# relays2.net
KiCad netlist of a schematic drawn in Altium Designer
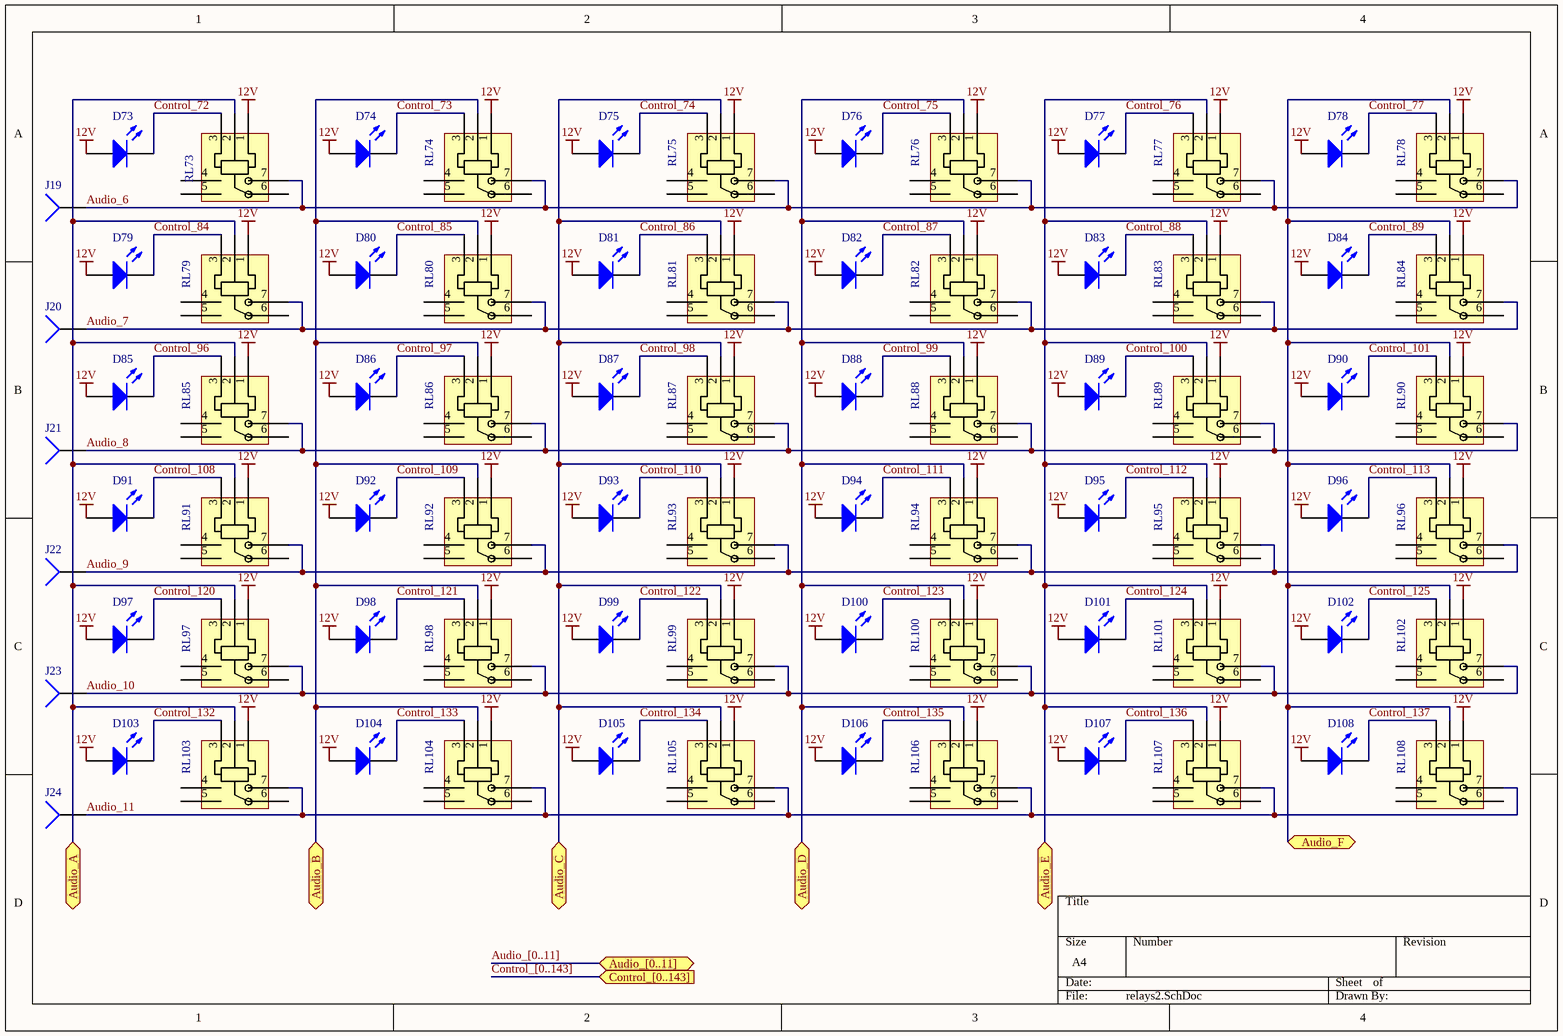
[diagram p0: relays2.SchDoc]

(export (version "E")
  (design (tool "Eeschema 10.0.6"))
  (components
    (comp (ref "D73")
      (value "LED0")
      (footprint "LED_round_5mm")
      (description "Typical INFRARED GaAs LED")
      (fields (field (name "PUBLISHER") "Altium Limited"))
      (libsource (lib "Miscellaneous Devices") (part "LED0"))
    )
    (comp (ref "D74")
      (value "LED0")
      (footprint "LED_round_5mm")
      (description "Typical INFRARED GaAs LED")
      (fields (field (name "PUBLISHER") "Altium Limited"))
      (libsource (lib "Miscellaneous Devices") (part "LED0"))
    )
    (comp (ref "D75")
      (value "LED0")
      (footprint "LED_round_5mm")
      (description "Typical INFRARED GaAs LED")
      (fields (field (name "PUBLISHER") "Altium Limited"))
      (libsource (lib "Miscellaneous Devices") (part "LED0"))
    )
    (comp (ref "D76")
      (value "LED0")
      (footprint "LED_round_5mm")
      (description "Typical INFRARED GaAs LED")
      (fields (field (name "PUBLISHER") "Altium Limited"))
      (libsource (lib "Miscellaneous Devices") (part "LED0"))
    )
    (comp (ref "D77")
      (value "LED0")
      (footprint "LED_round_5mm")
      (description "Typical INFRARED GaAs LED")
      (fields (field (name "PUBLISHER") "Altium Limited"))
      (libsource (lib "Miscellaneous Devices") (part "LED0"))
    )
    (comp (ref "D78")
      (value "LED0")
      (footprint "LED_round_5mm")
      (description "Typical INFRARED GaAs LED")
      (fields (field (name "PUBLISHER") "Altium Limited"))
      (libsource (lib "Miscellaneous Devices") (part "LED0"))
    )
    (comp (ref "D79")
      (value "LED0")
      (footprint "LED_round_5mm")
      (description "Typical INFRARED GaAs LED")
      (fields (field (name "PUBLISHER") "Altium Limited"))
      (libsource (lib "Miscellaneous Devices") (part "LED0"))
    )
    (comp (ref "D80")
      (value "LED0")
      (footprint "LED_round_5mm")
      (description "Typical INFRARED GaAs LED")
      (fields (field (name "PUBLISHER") "Altium Limited"))
      (libsource (lib "Miscellaneous Devices") (part "LED0"))
    )
    (comp (ref "D81")
      (value "LED0")
      (footprint "LED_round_5mm")
      (description "Typical INFRARED GaAs LED")
      (fields (field (name "PUBLISHER") "Altium Limited"))
      (libsource (lib "Miscellaneous Devices") (part "LED0"))
    )
    (comp (ref "D82")
      (value "LED0")
      (footprint "LED_round_5mm")
      (description "Typical INFRARED GaAs LED")
      (fields (field (name "PUBLISHER") "Altium Limited"))
      (libsource (lib "Miscellaneous Devices") (part "LED0"))
    )
    (comp (ref "D83")
      (value "LED0")
      (footprint "LED_round_5mm")
      (description "Typical INFRARED GaAs LED")
      (fields (field (name "PUBLISHER") "Altium Limited"))
      (libsource (lib "Miscellaneous Devices") (part "LED0"))
    )
    (comp (ref "D84")
      (value "LED0")
      (footprint "LED_round_5mm")
      (description "Typical INFRARED GaAs LED")
      (fields (field (name "PUBLISHER") "Altium Limited"))
      (libsource (lib "Miscellaneous Devices") (part "LED0"))
    )
    (comp (ref "D85")
      (value "LED0")
      (footprint "LED_round_5mm")
      (description "Typical INFRARED GaAs LED")
      (fields (field (name "PUBLISHER") "Altium Limited"))
      (libsource (lib "Miscellaneous Devices") (part "LED0"))
    )
    (comp (ref "D86")
      (value "LED0")
      (footprint "LED_round_5mm")
      (description "Typical INFRARED GaAs LED")
      (fields (field (name "PUBLISHER") "Altium Limited"))
      (libsource (lib "Miscellaneous Devices") (part "LED0"))
    )
    (comp (ref "D87")
      (value "LED0")
      (footprint "LED_round_5mm")
      (description "Typical INFRARED GaAs LED")
      (fields (field (name "PUBLISHER") "Altium Limited"))
      (libsource (lib "Miscellaneous Devices") (part "LED0"))
    )
    (comp (ref "D88")
      (value "LED0")
      (footprint "LED_round_5mm")
      (description "Typical INFRARED GaAs LED")
      (fields (field (name "PUBLISHER") "Altium Limited"))
      (libsource (lib "Miscellaneous Devices") (part "LED0"))
    )
    (comp (ref "D89")
      (value "LED0")
      (footprint "LED_round_5mm")
      (description "Typical INFRARED GaAs LED")
      (fields (field (name "PUBLISHER") "Altium Limited"))
      (libsource (lib "Miscellaneous Devices") (part "LED0"))
    )
    (comp (ref "D90")
      (value "LED0")
      (footprint "LED_round_5mm")
      (description "Typical INFRARED GaAs LED")
      (fields (field (name "PUBLISHER") "Altium Limited"))
      (libsource (lib "Miscellaneous Devices") (part "LED0"))
    )
    (comp (ref "D91")
      (value "LED0")
      (footprint "LED_round_5mm")
      (description "Typical INFRARED GaAs LED")
      (fields (field (name "PUBLISHER") "Altium Limited"))
      (libsource (lib "Miscellaneous Devices") (part "LED0"))
    )
    (comp (ref "D92")
      (value "LED0")
      (footprint "LED_round_5mm")
      (description "Typical INFRARED GaAs LED")
      (fields (field (name "PUBLISHER") "Altium Limited"))
      (libsource (lib "Miscellaneous Devices") (part "LED0"))
    )
    (comp (ref "D93")
      (value "LED0")
      (footprint "LED_round_5mm")
      (description "Typical INFRARED GaAs LED")
      (fields (field (name "PUBLISHER") "Altium Limited"))
      (libsource (lib "Miscellaneous Devices") (part "LED0"))
    )
    (comp (ref "D94")
      (value "LED0")
      (footprint "LED_round_5mm")
      (description "Typical INFRARED GaAs LED")
      (fields (field (name "PUBLISHER") "Altium Limited"))
      (libsource (lib "Miscellaneous Devices") (part "LED0"))
    )
    (comp (ref "D95")
      (value "LED0")
      (footprint "LED_round_5mm")
      (description "Typical INFRARED GaAs LED")
      (fields (field (name "PUBLISHER") "Altium Limited"))
      (libsource (lib "Miscellaneous Devices") (part "LED0"))
    )
    (comp (ref "D96")
      (value "LED0")
      (footprint "LED_round_5mm")
      (description "Typical INFRARED GaAs LED")
      (fields (field (name "PUBLISHER") "Altium Limited"))
      (libsource (lib "Miscellaneous Devices") (part "LED0"))
    )
    (comp (ref "D97")
      (value "LED0")
      (footprint "LED_round_5mm")
      (description "Typical INFRARED GaAs LED")
      (fields (field (name "PUBLISHER") "Altium Limited"))
      (libsource (lib "Miscellaneous Devices") (part "LED0"))
    )
    (comp (ref "D98")
      (value "LED0")
      (footprint "LED_round_5mm")
      (description "Typical INFRARED GaAs LED")
      (fields (field (name "PUBLISHER") "Altium Limited"))
      (libsource (lib "Miscellaneous Devices") (part "LED0"))
    )
    (comp (ref "D99")
      (value "LED0")
      (footprint "LED_round_5mm")
      (description "Typical INFRARED GaAs LED")
      (fields (field (name "PUBLISHER") "Altium Limited"))
      (libsource (lib "Miscellaneous Devices") (part "LED0"))
    )
    (comp (ref "D100")
      (value "LED0")
      (footprint "LED_round_5mm")
      (description "Typical INFRARED GaAs LED")
      (fields (field (name "PUBLISHER") "Altium Limited"))
      (libsource (lib "Miscellaneous Devices") (part "LED0"))
    )
    (comp (ref "D101")
      (value "LED0")
      (footprint "LED_round_5mm")
      (description "Typical INFRARED GaAs LED")
      (fields (field (name "PUBLISHER") "Altium Limited"))
      (libsource (lib "Miscellaneous Devices") (part "LED0"))
    )
    (comp (ref "D102")
      (value "LED0")
      (footprint "LED_round_5mm")
      (description "Typical INFRARED GaAs LED")
      (fields (field (name "PUBLISHER") "Altium Limited"))
      (libsource (lib "Miscellaneous Devices") (part "LED0"))
    )
    (comp (ref "D103")
      (value "LED0")
      (footprint "LED_round_5mm")
      (description "Typical INFRARED GaAs LED")
      (fields (field (name "PUBLISHER") "Altium Limited"))
      (libsource (lib "Miscellaneous Devices") (part "LED0"))
    )
    (comp (ref "D104")
      (value "LED0")
      (footprint "LED_round_5mm")
      (description "Typical INFRARED GaAs LED")
      (fields (field (name "PUBLISHER") "Altium Limited"))
      (libsource (lib "Miscellaneous Devices") (part "LED0"))
    )
    (comp (ref "D105")
      (value "LED0")
      (footprint "LED_round_5mm")
      (description "Typical INFRARED GaAs LED")
      (fields (field (name "PUBLISHER") "Altium Limited"))
      (libsource (lib "Miscellaneous Devices") (part "LED0"))
    )
    (comp (ref "D106")
      (value "LED0")
      (footprint "LED_round_5mm")
      (description "Typical INFRARED GaAs LED")
      (fields (field (name "PUBLISHER") "Altium Limited"))
      (libsource (lib "Miscellaneous Devices") (part "LED0"))
    )
    (comp (ref "D107")
      (value "LED0")
      (footprint "LED_round_5mm")
      (description "Typical INFRARED GaAs LED")
      (fields (field (name "PUBLISHER") "Altium Limited"))
      (libsource (lib "Miscellaneous Devices") (part "LED0"))
    )
    (comp (ref "D108")
      (value "LED0")
      (footprint "LED_round_5mm")
      (description "Typical INFRARED GaAs LED")
      (fields (field (name "PUBLISHER") "Altium Limited"))
      (libsource (lib "Miscellaneous Devices") (part "LED0"))
    )
    (comp (ref "J19")
      (value "Audio")
      (footprint "Conn_1_2x4")
      (description "Socket")
      (fields (field (name "PUBLISHER") "Altium Limited"))
      (libsource (lib "Miscellaneous Connectors") (part "Socket"))
    )
    (comp (ref "J20")
      (value "Audio")
      (footprint "Conn_1_2x4")
      (description "Socket")
      (fields (field (name "PUBLISHER") "Altium Limited"))
      (libsource (lib "Miscellaneous Connectors") (part "Socket"))
    )
    (comp (ref "J21")
      (value "Audio")
      (footprint "Conn_1_2x4")
      (description "Socket")
      (fields (field (name "PUBLISHER") "Altium Limited"))
      (libsource (lib "Miscellaneous Connectors") (part "Socket"))
    )
    (comp (ref "J22")
      (value "Audio")
      (footprint "Conn_1_2x4")
      (description "Socket")
      (fields (field (name "PUBLISHER") "Altium Limited"))
      (libsource (lib "Miscellaneous Connectors") (part "Socket"))
    )
    (comp (ref "J23")
      (value "Audio")
      (footprint "Conn_1_2x4")
      (description "Socket")
      (fields (field (name "PUBLISHER") "Altium Limited"))
      (libsource (lib "Miscellaneous Connectors") (part "Socket"))
    )
    (comp (ref "J24")
      (value "Audio")
      (footprint "Conn_1_2x4")
      (description "Socket")
      (fields (field (name "PUBLISHER") "Altium Limited"))
      (libsource (lib "Miscellaneous Connectors") (part "Socket"))
    )
    (comp (ref "RL73")
      (value "Relay")
      (footprint "Relay_FRA3")
      (description "Miniature power relay")
      (fields (field (name "PART NUMBER") "FRA3C-DC12"))
      (libsource (lib "tech-thing") (part "Relay_FRA3"))
    )
    (comp (ref "RL74")
      (value "Relay")
      (footprint "Relay_FRA3")
      (description "Miniature power relay")
      (fields (field (name "PART NUMBER") "FRA3C-DC12"))
      (libsource (lib "tech-thing") (part "Relay_FRA3"))
    )
    (comp (ref "RL75")
      (value "Relay")
      (footprint "Relay_FRA3")
      (description "Miniature power relay")
      (fields (field (name "PART NUMBER") "FRA3C-DC12"))
      (libsource (lib "tech-thing") (part "Relay_FRA3"))
    )
    (comp (ref "RL76")
      (value "Relay")
      (footprint "Relay_FRA3")
      (description "Miniature power relay")
      (fields (field (name "PART NUMBER") "FRA3C-DC12"))
      (libsource (lib "tech-thing") (part "Relay_FRA3"))
    )
    (comp (ref "RL77")
      (value "Relay")
      (footprint "Relay_FRA3")
      (description "Miniature power relay")
      (fields (field (name "PART NUMBER") "FRA3C-DC12"))
      (libsource (lib "tech-thing") (part "Relay_FRA3"))
    )
    (comp (ref "RL78")
      (value "Relay")
      (footprint "Relay_FRA3")
      (description "Miniature power relay")
      (fields (field (name "PART NUMBER") "FRA3C-DC12"))
      (libsource (lib "tech-thing") (part "Relay_FRA3"))
    )
    (comp (ref "RL79")
      (value "Relay")
      (footprint "Relay_FRA3")
      (description "Miniature power relay")
      (fields (field (name "PART NUMBER") "FRA3C-DC12"))
      (libsource (lib "tech-thing") (part "Relay_FRA3"))
    )
    (comp (ref "RL80")
      (value "Relay")
      (footprint "Relay_FRA3")
      (description "Miniature power relay")
      (fields (field (name "PART NUMBER") "FRA3C-DC12"))
      (libsource (lib "tech-thing") (part "Relay_FRA3"))
    )
    (comp (ref "RL81")
      (value "Relay")
      (footprint "Relay_FRA3")
      (description "Miniature power relay")
      (fields (field (name "PART NUMBER") "FRA3C-DC12"))
      (libsource (lib "tech-thing") (part "Relay_FRA3"))
    )
    (comp (ref "RL82")
      (value "Relay")
      (footprint "Relay_FRA3")
      (description "Miniature power relay")
      (fields (field (name "PART NUMBER") "FRA3C-DC12"))
      (libsource (lib "tech-thing") (part "Relay_FRA3"))
    )
    (comp (ref "RL83")
      (value "Relay")
      (footprint "Relay_FRA3")
      (description "Miniature power relay")
      (fields (field (name "PART NUMBER") "FRA3C-DC12"))
      (libsource (lib "tech-thing") (part "Relay_FRA3"))
    )
    (comp (ref "RL84")
      (value "Relay")
      (footprint "Relay_FRA3")
      (description "Miniature power relay")
      (fields (field (name "PART NUMBER") "FRA3C-DC12"))
      (libsource (lib "tech-thing") (part "Relay_FRA3"))
    )
    (comp (ref "RL85")
      (value "Relay")
      (footprint "Relay_FRA3")
      (description "Miniature power relay")
      (fields (field (name "PART NUMBER") "FRA3C-DC12"))
      (libsource (lib "tech-thing") (part "Relay_FRA3"))
    )
    (comp (ref "RL86")
      (value "Relay")
      (footprint "Relay_FRA3")
      (description "Miniature power relay")
      (fields (field (name "PART NUMBER") "FRA3C-DC12"))
      (libsource (lib "tech-thing") (part "Relay_FRA3"))
    )
    (comp (ref "RL87")
      (value "Relay")
      (footprint "Relay_FRA3")
      (description "Miniature power relay")
      (fields (field (name "PART NUMBER") "FRA3C-DC12"))
      (libsource (lib "tech-thing") (part "Relay_FRA3"))
    )
    (comp (ref "RL88")
      (value "Relay")
      (footprint "Relay_FRA3")
      (description "Miniature power relay")
      (fields (field (name "PART NUMBER") "FRA3C-DC12"))
      (libsource (lib "tech-thing") (part "Relay_FRA3"))
    )
    (comp (ref "RL89")
      (value "Relay")
      (footprint "Relay_FRA3")
      (description "Miniature power relay")
      (fields (field (name "PART NUMBER") "FRA3C-DC12"))
      (libsource (lib "tech-thing") (part "Relay_FRA3"))
    )
    (comp (ref "RL90")
      (value "Relay")
      (footprint "Relay_FRA3")
      (description "Miniature power relay")
      (fields (field (name "PART NUMBER") "FRA3C-DC12"))
      (libsource (lib "tech-thing") (part "Relay_FRA3"))
    )
    (comp (ref "RL91")
      (value "Relay")
      (footprint "Relay_FRA3")
      (description "Miniature power relay")
      (fields (field (name "PART NUMBER") "FRA3C-DC12"))
      (libsource (lib "tech-thing") (part "Relay_FRA3"))
    )
    (comp (ref "RL92")
      (value "Relay")
      (footprint "Relay_FRA3")
      (description "Miniature power relay")
      (fields (field (name "PART NUMBER") "FRA3C-DC12"))
      (libsource (lib "tech-thing") (part "Relay_FRA3"))
    )
    (comp (ref "RL93")
      (value "Relay")
      (footprint "Relay_FRA3")
      (description "Miniature power relay")
      (fields (field (name "PART NUMBER") "FRA3C-DC12"))
      (libsource (lib "tech-thing") (part "Relay_FRA3"))
    )
    (comp (ref "RL94")
      (value "Relay")
      (footprint "Relay_FRA3")
      (description "Miniature power relay")
      (fields (field (name "PART NUMBER") "FRA3C-DC12"))
      (libsource (lib "tech-thing") (part "Relay_FRA3"))
    )
    (comp (ref "RL95")
      (value "Relay")
      (footprint "Relay_FRA3")
      (description "Miniature power relay")
      (fields (field (name "PART NUMBER") "FRA3C-DC12"))
      (libsource (lib "tech-thing") (part "Relay_FRA3"))
    )
    (comp (ref "RL96")
      (value "Relay")
      (footprint "Relay_FRA3")
      (description "Miniature power relay")
      (fields (field (name "PART NUMBER") "FRA3C-DC12"))
      (libsource (lib "tech-thing") (part "Relay_FRA3"))
    )
    (comp (ref "RL97")
      (value "Relay")
      (footprint "Relay_FRA3")
      (description "Miniature power relay")
      (fields (field (name "PART NUMBER") "FRA3C-DC12"))
      (libsource (lib "tech-thing") (part "Relay_FRA3"))
    )
    (comp (ref "RL98")
      (value "Relay")
      (footprint "Relay_FRA3")
      (description "Miniature power relay")
      (fields (field (name "PART NUMBER") "FRA3C-DC12"))
      (libsource (lib "tech-thing") (part "Relay_FRA3"))
    )
    (comp (ref "RL99")
      (value "Relay")
      (footprint "Relay_FRA3")
      (description "Miniature power relay")
      (fields (field (name "PART NUMBER") "FRA3C-DC12"))
      (libsource (lib "tech-thing") (part "Relay_FRA3"))
    )
    (comp (ref "RL100")
      (value "Relay")
      (footprint "Relay_FRA3")
      (description "Miniature power relay")
      (fields (field (name "PART NUMBER") "FRA3C-DC12"))
      (libsource (lib "tech-thing") (part "Relay_FRA3"))
    )
    (comp (ref "RL101")
      (value "Relay")
      (footprint "Relay_FRA3")
      (description "Miniature power relay")
      (fields (field (name "PART NUMBER") "FRA3C-DC12"))
      (libsource (lib "tech-thing") (part "Relay_FRA3"))
    )
    (comp (ref "RL102")
      (value "Relay")
      (footprint "Relay_FRA3")
      (description "Miniature power relay")
      (fields (field (name "PART NUMBER") "FRA3C-DC12"))
      (libsource (lib "tech-thing") (part "Relay_FRA3"))
    )
    (comp (ref "RL103")
      (value "Relay")
      (footprint "Relay_FRA3")
      (description "Miniature power relay")
      (fields (field (name "PART NUMBER") "FRA3C-DC12"))
      (libsource (lib "tech-thing") (part "Relay_FRA3"))
    )
    (comp (ref "RL104")
      (value "Relay")
      (footprint "Relay_FRA3")
      (description "Miniature power relay")
      (fields (field (name "PART NUMBER") "FRA3C-DC12"))
      (libsource (lib "tech-thing") (part "Relay_FRA3"))
    )
    (comp (ref "RL105")
      (value "Relay")
      (footprint "Relay_FRA3")
      (description "Miniature power relay")
      (fields (field (name "PART NUMBER") "FRA3C-DC12"))
      (libsource (lib "tech-thing") (part "Relay_FRA3"))
    )
    (comp (ref "RL106")
      (value "Relay")
      (footprint "Relay_FRA3")
      (description "Miniature power relay")
      (fields (field (name "PART NUMBER") "FRA3C-DC12"))
      (libsource (lib "tech-thing") (part "Relay_FRA3"))
    )
    (comp (ref "RL107")
      (value "Relay")
      (footprint "Relay_FRA3")
      (description "Miniature power relay")
      (fields (field (name "PART NUMBER") "FRA3C-DC12"))
      (libsource (lib "tech-thing") (part "Relay_FRA3"))
    )
    (comp (ref "RL108")
      (value "Relay")
      (footprint "Relay_FRA3")
      (description "Miniature power relay")
      (fields (field (name "PART NUMBER") "FRA3C-DC12"))
      (libsource (lib "tech-thing") (part "Relay_FRA3"))
    )
  )
  (nets
    (net (code "115") (name "/Audio_6") (class "Default")
      (node (ref "J19") (pin "1") (pinfunction "1_1") (pintype "passive"))
      (node (ref "RL73") (pin "7") (pintype "passive"))
      (node (ref "RL74") (pin "7") (pintype "passive"))
      (node (ref "RL75") (pin "7") (pintype "passive"))
      (node (ref "RL76") (pin "7") (pintype "passive"))
      (node (ref "RL77") (pin "7") (pintype "passive"))
      (node (ref "RL78") (pin "7") (pintype "passive"))
    )
    (net (code "116") (name "/Audio_7") (class "Default")
      (node (ref "J20") (pin "1") (pinfunction "1_1") (pintype "passive"))
      (node (ref "RL79") (pin "7") (pintype "passive"))
      (node (ref "RL80") (pin "7") (pintype "passive"))
      (node (ref "RL81") (pin "7") (pintype "passive"))
      (node (ref "RL82") (pin "7") (pintype "passive"))
      (node (ref "RL83") (pin "7") (pintype "passive"))
      (node (ref "RL84") (pin "7") (pintype "passive"))
    )
    (net (code "117") (name "/Audio_8") (class "Default")
      (node (ref "J21") (pin "1") (pinfunction "1_1") (pintype "passive"))
      (node (ref "RL85") (pin "7") (pintype "passive"))
      (node (ref "RL86") (pin "7") (pintype "passive"))
      (node (ref "RL87") (pin "7") (pintype "passive"))
      (node (ref "RL88") (pin "7") (pintype "passive"))
      (node (ref "RL89") (pin "7") (pintype "passive"))
      (node (ref "RL90") (pin "7") (pintype "passive"))
    )
    (net (code "118") (name "/Audio_9") (class "Default")
      (node (ref "J22") (pin "1") (pinfunction "1_1") (pintype "passive"))
      (node (ref "RL91") (pin "7") (pintype "passive"))
      (node (ref "RL92") (pin "7") (pintype "passive"))
      (node (ref "RL93") (pin "7") (pintype "passive"))
      (node (ref "RL94") (pin "7") (pintype "passive"))
      (node (ref "RL95") (pin "7") (pintype "passive"))
      (node (ref "RL96") (pin "7") (pintype "passive"))
    )
    (net (code "119") (name "/Audio_10") (class "Default")
      (node (ref "J23") (pin "1") (pinfunction "1_1") (pintype "passive"))
      (node (ref "RL100") (pin "7") (pintype "passive"))
      (node (ref "RL101") (pin "7") (pintype "passive"))
      (node (ref "RL102") (pin "7") (pintype "passive"))
      (node (ref "RL97") (pin "7") (pintype "passive"))
      (node (ref "RL98") (pin "7") (pintype "passive"))
      (node (ref "RL99") (pin "7") (pintype "passive"))
    )
    (net (code "120") (name "/Audio_11") (class "Default")
      (node (ref "J24") (pin "1") (pinfunction "1_1") (pintype "passive"))
      (node (ref "RL103") (pin "7") (pintype "passive"))
      (node (ref "RL104") (pin "7") (pintype "passive"))
      (node (ref "RL105") (pin "7") (pintype "passive"))
      (node (ref "RL106") (pin "7") (pintype "passive"))
      (node (ref "RL107") (pin "7") (pintype "passive"))
      (node (ref "RL108") (pin "7") (pintype "passive"))
    )
    (net (code "121") (name "/Audio_A") (class "Default")
      (node (ref "RL103") (pin "2") (pintype "passive"))
      (node (ref "RL73") (pin "2") (pintype "passive"))
      (node (ref "RL79") (pin "2") (pintype "passive"))
      (node (ref "RL85") (pin "2") (pintype "passive"))
      (node (ref "RL91") (pin "2") (pintype "passive"))
      (node (ref "RL97") (pin "2") (pintype "passive"))
    )
    (net (code "122") (name "/Audio_B") (class "Default")
      (node (ref "RL104") (pin "2") (pintype "passive"))
      (node (ref "RL74") (pin "2") (pintype "passive"))
      (node (ref "RL80") (pin "2") (pintype "passive"))
      (node (ref "RL86") (pin "2") (pintype "passive"))
      (node (ref "RL92") (pin "2") (pintype "passive"))
      (node (ref "RL98") (pin "2") (pintype "passive"))
    )
    (net (code "123") (name "/Audio_C") (class "Default")
      (node (ref "RL105") (pin "2") (pintype "passive"))
      (node (ref "RL75") (pin "2") (pintype "passive"))
      (node (ref "RL81") (pin "2") (pintype "passive"))
      (node (ref "RL87") (pin "2") (pintype "passive"))
      (node (ref "RL93") (pin "2") (pintype "passive"))
      (node (ref "RL99") (pin "2") (pintype "passive"))
    )
    (net (code "124") (name "/Audio_D") (class "Default")
      (node (ref "RL100") (pin "2") (pintype "passive"))
      (node (ref "RL106") (pin "2") (pintype "passive"))
      (node (ref "RL76") (pin "2") (pintype "passive"))
      (node (ref "RL82") (pin "2") (pintype "passive"))
      (node (ref "RL88") (pin "2") (pintype "passive"))
      (node (ref "RL94") (pin "2") (pintype "passive"))
    )
    (net (code "125") (name "/Audio_E") (class "Default")
      (node (ref "RL101") (pin "2") (pintype "passive"))
      (node (ref "RL107") (pin "2") (pintype "passive"))
      (node (ref "RL77") (pin "2") (pintype "passive"))
      (node (ref "RL83") (pin "2") (pintype "passive"))
      (node (ref "RL89") (pin "2") (pintype "passive"))
      (node (ref "RL95") (pin "2") (pintype "passive"))
    )
    (net (code "126") (name "/Audio_F") (class "Default")
      (node (ref "RL102") (pin "2") (pintype "passive"))
      (node (ref "RL108") (pin "2") (pintype "passive"))
      (node (ref "RL78") (pin "2") (pintype "passive"))
      (node (ref "RL84") (pin "2") (pintype "passive"))
      (node (ref "RL90") (pin "2") (pintype "passive"))
      (node (ref "RL96") (pin "2") (pintype "passive"))
    )
    (net (code "128") (name "/Control_72") (class "Default")
      (node (ref "D73") (pin "2") (pinfunction "K_2") (pintype "passive"))
      (node (ref "RL73") (pin "3") (pintype "passive"))
    )
    (net (code "129") (name "/Control_73") (class "Default")
      (node (ref "D74") (pin "2") (pinfunction "K_2") (pintype "passive"))
      (node (ref "RL74") (pin "3") (pintype "passive"))
    )
    (net (code "130") (name "/Control_74") (class "Default")
      (node (ref "D75") (pin "2") (pinfunction "K_2") (pintype "passive"))
      (node (ref "RL75") (pin "3") (pintype "passive"))
    )
    (net (code "131") (name "/Control_75") (class "Default")
      (node (ref "D76") (pin "2") (pinfunction "K_2") (pintype "passive"))
      (node (ref "RL76") (pin "3") (pintype "passive"))
    )
    (net (code "132") (name "/Control_76") (class "Default")
      (node (ref "D77") (pin "2") (pinfunction "K_2") (pintype "passive"))
      (node (ref "RL77") (pin "3") (pintype "passive"))
    )
    (net (code "133") (name "/Control_77") (class "Default")
      (node (ref "D78") (pin "2") (pinfunction "K_2") (pintype "passive"))
      (node (ref "RL78") (pin "3") (pintype "passive"))
    )
    (net (code "134") (name "/Control_84") (class "Default")
      (node (ref "D79") (pin "2") (pinfunction "K_2") (pintype "passive"))
      (node (ref "RL79") (pin "3") (pintype "passive"))
    )
    (net (code "135") (name "/Control_85") (class "Default")
      (node (ref "D80") (pin "2") (pinfunction "K_2") (pintype "passive"))
      (node (ref "RL80") (pin "3") (pintype "passive"))
    )
    (net (code "136") (name "/Control_86") (class "Default")
      (node (ref "D81") (pin "2") (pinfunction "K_2") (pintype "passive"))
      (node (ref "RL81") (pin "3") (pintype "passive"))
    )
    (net (code "137") (name "/Control_87") (class "Default")
      (node (ref "D82") (pin "2") (pinfunction "K_2") (pintype "passive"))
      (node (ref "RL82") (pin "3") (pintype "passive"))
    )
    (net (code "138") (name "/Control_88") (class "Default")
      (node (ref "D83") (pin "2") (pinfunction "K_2") (pintype "passive"))
      (node (ref "RL83") (pin "3") (pintype "passive"))
    )
    (net (code "139") (name "/Control_89") (class "Default")
      (node (ref "D84") (pin "2") (pinfunction "K_2") (pintype "passive"))
      (node (ref "RL84") (pin "3") (pintype "passive"))
    )
    (net (code "140") (name "/Control_96") (class "Default")
      (node (ref "D85") (pin "2") (pinfunction "K_2") (pintype "passive"))
      (node (ref "RL85") (pin "3") (pintype "passive"))
    )
    (net (code "141") (name "/Control_97") (class "Default")
      (node (ref "D86") (pin "2") (pinfunction "K_2") (pintype "passive"))
      (node (ref "RL86") (pin "3") (pintype "passive"))
    )
    (net (code "142") (name "/Control_98") (class "Default")
      (node (ref "D87") (pin "2") (pinfunction "K_2") (pintype "passive"))
      (node (ref "RL87") (pin "3") (pintype "passive"))
    )
    (net (code "143") (name "/Control_99") (class "Default")
      (node (ref "D88") (pin "2") (pinfunction "K_2") (pintype "passive"))
      (node (ref "RL88") (pin "3") (pintype "passive"))
    )
    (net (code "144") (name "/Control_100") (class "Default")
      (node (ref "D89") (pin "2") (pinfunction "K_2") (pintype "passive"))
      (node (ref "RL89") (pin "3") (pintype "passive"))
    )
    (net (code "145") (name "/Control_101") (class "Default")
      (node (ref "D90") (pin "2") (pinfunction "K_2") (pintype "passive"))
      (node (ref "RL90") (pin "3") (pintype "passive"))
    )
    (net (code "146") (name "/Control_108") (class "Default")
      (node (ref "D91") (pin "2") (pinfunction "K_2") (pintype "passive"))
      (node (ref "RL91") (pin "3") (pintype "passive"))
    )
    (net (code "147") (name "/Control_109") (class "Default")
      (node (ref "D92") (pin "2") (pinfunction "K_2") (pintype "passive"))
      (node (ref "RL92") (pin "3") (pintype "passive"))
    )
    (net (code "148") (name "/Control_110") (class "Default")
      (node (ref "D93") (pin "2") (pinfunction "K_2") (pintype "passive"))
      (node (ref "RL93") (pin "3") (pintype "passive"))
    )
    (net (code "149") (name "/Control_111") (class "Default")
      (node (ref "D94") (pin "2") (pinfunction "K_2") (pintype "passive"))
      (node (ref "RL94") (pin "3") (pintype "passive"))
    )
    (net (code "150") (name "/Control_112") (class "Default")
      (node (ref "D95") (pin "2") (pinfunction "K_2") (pintype "passive"))
      (node (ref "RL95") (pin "3") (pintype "passive"))
    )
    (net (code "151") (name "/Control_113") (class "Default")
      (node (ref "D96") (pin "2") (pinfunction "K_2") (pintype "passive"))
      (node (ref "RL96") (pin "3") (pintype "passive"))
    )
    (net (code "152") (name "/Control_120") (class "Default")
      (node (ref "D97") (pin "2") (pinfunction "K_2") (pintype "passive"))
      (node (ref "RL97") (pin "3") (pintype "passive"))
    )
    (net (code "153") (name "/Control_121") (class "Default")
      (node (ref "D98") (pin "2") (pinfunction "K_2") (pintype "passive"))
      (node (ref "RL98") (pin "3") (pintype "passive"))
    )
    (net (code "154") (name "/Control_122") (class "Default")
      (node (ref "D99") (pin "2") (pinfunction "K_2") (pintype "passive"))
      (node (ref "RL99") (pin "3") (pintype "passive"))
    )
    (net (code "155") (name "/Control_123") (class "Default")
      (node (ref "D100") (pin "2") (pinfunction "K_2") (pintype "passive"))
      (node (ref "RL100") (pin "3") (pintype "passive"))
    )
    (net (code "156") (name "/Control_124") (class "Default")
      (node (ref "D101") (pin "2") (pinfunction "K_2") (pintype "passive"))
      (node (ref "RL101") (pin "3") (pintype "passive"))
    )
    (net (code "157") (name "/Control_125") (class "Default")
      (node (ref "D102") (pin "2") (pinfunction "K_2") (pintype "passive"))
      (node (ref "RL102") (pin "3") (pintype "passive"))
    )
    (net (code "158") (name "/Control_132") (class "Default")
      (node (ref "D103") (pin "2") (pinfunction "K_2") (pintype "passive"))
      (node (ref "RL103") (pin "3") (pintype "passive"))
    )
    (net (code "159") (name "/Control_133") (class "Default")
      (node (ref "D104") (pin "2") (pinfunction "K_2") (pintype "passive"))
      (node (ref "RL104") (pin "3") (pintype "passive"))
    )
    (net (code "160") (name "/Control_134") (class "Default")
      (node (ref "D105") (pin "2") (pinfunction "K_2") (pintype "passive"))
      (node (ref "RL105") (pin "3") (pintype "passive"))
    )
    (net (code "161") (name "/Control_135") (class "Default")
      (node (ref "D106") (pin "2") (pinfunction "K_2") (pintype "passive"))
      (node (ref "RL106") (pin "3") (pintype "passive"))
    )
    (net (code "162") (name "/Control_136") (class "Default")
      (node (ref "D107") (pin "2") (pinfunction "K_2") (pintype "passive"))
      (node (ref "RL107") (pin "3") (pintype "passive"))
    )
    (net (code "163") (name "/Control_137") (class "Default")
      (node (ref "D108") (pin "2") (pinfunction "K_2") (pintype "passive"))
      (node (ref "RL108") (pin "3") (pintype "passive"))
    )
    (net (code "165") (name "12V") (class "Default")
      (node (ref "D100") (pin "1") (pinfunction "A_1") (pintype "passive"))
      (node (ref "D101") (pin "1") (pinfunction "A_1") (pintype "passive"))
      (node (ref "D102") (pin "1") (pinfunction "A_1") (pintype "passive"))
      (node (ref "D103") (pin "1") (pinfunction "A_1") (pintype "passive"))
      (node (ref "D104") (pin "1") (pinfunction "A_1") (pintype "passive"))
      (node (ref "D105") (pin "1") (pinfunction "A_1") (pintype "passive"))
      (node (ref "D106") (pin "1") (pinfunction "A_1") (pintype "passive"))
      (node (ref "D107") (pin "1") (pinfunction "A_1") (pintype "passive"))
      (node (ref "D108") (pin "1") (pinfunction "A_1") (pintype "passive"))
      (node (ref "D73") (pin "1") (pinfunction "A_1") (pintype "passive"))
      (node (ref "D74") (pin "1") (pinfunction "A_1") (pintype "passive"))
      (node (ref "D75") (pin "1") (pinfunction "A_1") (pintype "passive"))
      (node (ref "D76") (pin "1") (pinfunction "A_1") (pintype "passive"))
      (node (ref "D77") (pin "1") (pinfunction "A_1") (pintype "passive"))
      (node (ref "D78") (pin "1") (pinfunction "A_1") (pintype "passive"))
      (node (ref "D79") (pin "1") (pinfunction "A_1") (pintype "passive"))
      (node (ref "D80") (pin "1") (pinfunction "A_1") (pintype "passive"))
      (node (ref "D81") (pin "1") (pinfunction "A_1") (pintype "passive"))
      (node (ref "D82") (pin "1") (pinfunction "A_1") (pintype "passive"))
      (node (ref "D83") (pin "1") (pinfunction "A_1") (pintype "passive"))
      (node (ref "D84") (pin "1") (pinfunction "A_1") (pintype "passive"))
      (node (ref "D85") (pin "1") (pinfunction "A_1") (pintype "passive"))
      (node (ref "D86") (pin "1") (pinfunction "A_1") (pintype "passive"))
      (node (ref "D87") (pin "1") (pinfunction "A_1") (pintype "passive"))
      (node (ref "D88") (pin "1") (pinfunction "A_1") (pintype "passive"))
      (node (ref "D89") (pin "1") (pinfunction "A_1") (pintype "passive"))
      (node (ref "D90") (pin "1") (pinfunction "A_1") (pintype "passive"))
      (node (ref "D91") (pin "1") (pinfunction "A_1") (pintype "passive"))
      (node (ref "D92") (pin "1") (pinfunction "A_1") (pintype "passive"))
      (node (ref "D93") (pin "1") (pinfunction "A_1") (pintype "passive"))
      (node (ref "D94") (pin "1") (pinfunction "A_1") (pintype "passive"))
      (node (ref "D95") (pin "1") (pinfunction "A_1") (pintype "passive"))
      (node (ref "D96") (pin "1") (pinfunction "A_1") (pintype "passive"))
      (node (ref "D97") (pin "1") (pinfunction "A_1") (pintype "passive"))
      (node (ref "D98") (pin "1") (pinfunction "A_1") (pintype "passive"))
      (node (ref "D99") (pin "1") (pinfunction "A_1") (pintype "passive"))
      (node (ref "RL100") (pin "1") (pintype "passive"))
      (node (ref "RL101") (pin "1") (pintype "passive"))
      (node (ref "RL102") (pin "1") (pintype "passive"))
      (node (ref "RL103") (pin "1") (pintype "passive"))
      (node (ref "RL104") (pin "1") (pintype "passive"))
      (node (ref "RL105") (pin "1") (pintype "passive"))
      (node (ref "RL106") (pin "1") (pintype "passive"))
      (node (ref "RL107") (pin "1") (pintype "passive"))
      (node (ref "RL108") (pin "1") (pintype "passive"))
      (node (ref "RL73") (pin "1") (pintype "passive"))
      (node (ref "RL74") (pin "1") (pintype "passive"))
      (node (ref "RL75") (pin "1") (pintype "passive"))
      (node (ref "RL76") (pin "1") (pintype "passive"))
      (node (ref "RL77") (pin "1") (pintype "passive"))
      (node (ref "RL78") (pin "1") (pintype "passive"))
      (node (ref "RL79") (pin "1") (pintype "passive"))
      (node (ref "RL80") (pin "1") (pintype "passive"))
      (node (ref "RL81") (pin "1") (pintype "passive"))
      (node (ref "RL82") (pin "1") (pintype "passive"))
      (node (ref "RL83") (pin "1") (pintype "passive"))
      (node (ref "RL84") (pin "1") (pintype "passive"))
      (node (ref "RL85") (pin "1") (pintype "passive"))
      (node (ref "RL86") (pin "1") (pintype "passive"))
      (node (ref "RL87") (pin "1") (pintype "passive"))
      (node (ref "RL88") (pin "1") (pintype "passive"))
      (node (ref "RL89") (pin "1") (pintype "passive"))
      (node (ref "RL90") (pin "1") (pintype "passive"))
      (node (ref "RL91") (pin "1") (pintype "passive"))
      (node (ref "RL92") (pin "1") (pintype "passive"))
      (node (ref "RL93") (pin "1") (pintype "passive"))
      (node (ref "RL94") (pin "1") (pintype "passive"))
      (node (ref "RL95") (pin "1") (pintype "passive"))
      (node (ref "RL96") (pin "1") (pintype "passive"))
      (node (ref "RL97") (pin "1") (pintype "passive"))
      (node (ref "RL98") (pin "1") (pintype "passive"))
      (node (ref "RL99") (pin "1") (pintype "passive"))
    )
    (net (code "166") (name "unconnected-(RL73-Pad4)") (class "Default")
      (node (ref "RL73") (pin "4") (pintype "passive"))
    )
    (net (code "167") (name "unconnected-(RL73-Pad5)") (class "Default")
      (node (ref "RL73") (pin "5") (pintype "passive"))
    )
    (net (code "168") (name "unconnected-(RL73-Pad6)") (class "Default")
      (node (ref "RL73") (pin "6") (pintype "passive"))
    )
    (net (code "169") (name "unconnected-(RL74-Pad4)") (class "Default")
      (node (ref "RL74") (pin "4") (pintype "passive"))
    )
    (net (code "170") (name "unconnected-(RL74-Pad5)") (class "Default")
      (node (ref "RL74") (pin "5") (pintype "passive"))
    )
    (net (code "171") (name "unconnected-(RL74-Pad6)") (class "Default")
      (node (ref "RL74") (pin "6") (pintype "passive"))
    )
    (net (code "172") (name "unconnected-(RL75-Pad4)") (class "Default")
      (node (ref "RL75") (pin "4") (pintype "passive"))
    )
    (net (code "173") (name "unconnected-(RL75-Pad5)") (class "Default")
      (node (ref "RL75") (pin "5") (pintype "passive"))
    )
    (net (code "174") (name "unconnected-(RL75-Pad6)") (class "Default")
      (node (ref "RL75") (pin "6") (pintype "passive"))
    )
    (net (code "175") (name "unconnected-(RL76-Pad4)") (class "Default")
      (node (ref "RL76") (pin "4") (pintype "passive"))
    )
    (net (code "176") (name "unconnected-(RL76-Pad5)") (class "Default")
      (node (ref "RL76") (pin "5") (pintype "passive"))
    )
    (net (code "177") (name "unconnected-(RL76-Pad6)") (class "Default")
      (node (ref "RL76") (pin "6") (pintype "passive"))
    )
    (net (code "178") (name "unconnected-(RL77-Pad4)") (class "Default")
      (node (ref "RL77") (pin "4") (pintype "passive"))
    )
    (net (code "179") (name "unconnected-(RL77-Pad5)") (class "Default")
      (node (ref "RL77") (pin "5") (pintype "passive"))
    )
    (net (code "180") (name "unconnected-(RL77-Pad6)") (class "Default")
      (node (ref "RL77") (pin "6") (pintype "passive"))
    )
    (net (code "181") (name "unconnected-(RL78-Pad4)") (class "Default")
      (node (ref "RL78") (pin "4") (pintype "passive"))
    )
    (net (code "182") (name "unconnected-(RL78-Pad5)") (class "Default")
      (node (ref "RL78") (pin "5") (pintype "passive"))
    )
    (net (code "183") (name "unconnected-(RL78-Pad6)") (class "Default")
      (node (ref "RL78") (pin "6") (pintype "passive"))
    )
    (net (code "184") (name "unconnected-(RL79-Pad4)") (class "Default")
      (node (ref "RL79") (pin "4") (pintype "passive"))
    )
    (net (code "185") (name "unconnected-(RL79-Pad5)") (class "Default")
      (node (ref "RL79") (pin "5") (pintype "passive"))
    )
    (net (code "186") (name "unconnected-(RL79-Pad6)") (class "Default")
      (node (ref "RL79") (pin "6") (pintype "passive"))
    )
    (net (code "187") (name "unconnected-(RL80-Pad4)") (class "Default")
      (node (ref "RL80") (pin "4") (pintype "passive"))
    )
    (net (code "188") (name "unconnected-(RL80-Pad5)") (class "Default")
      (node (ref "RL80") (pin "5") (pintype "passive"))
    )
    (net (code "189") (name "unconnected-(RL80-Pad6)") (class "Default")
      (node (ref "RL80") (pin "6") (pintype "passive"))
    )
    (net (code "190") (name "unconnected-(RL81-Pad4)") (class "Default")
      (node (ref "RL81") (pin "4") (pintype "passive"))
    )
    (net (code "191") (name "unconnected-(RL81-Pad5)") (class "Default")
      (node (ref "RL81") (pin "5") (pintype "passive"))
    )
    (net (code "192") (name "unconnected-(RL81-Pad6)") (class "Default")
      (node (ref "RL81") (pin "6") (pintype "passive"))
    )
    (net (code "193") (name "unconnected-(RL82-Pad4)") (class "Default")
      (node (ref "RL82") (pin "4") (pintype "passive"))
    )
    (net (code "194") (name "unconnected-(RL82-Pad5)") (class "Default")
      (node (ref "RL82") (pin "5") (pintype "passive"))
    )
    (net (code "195") (name "unconnected-(RL82-Pad6)") (class "Default")
      (node (ref "RL82") (pin "6") (pintype "passive"))
    )
    (net (code "196") (name "unconnected-(RL83-Pad4)") (class "Default")
      (node (ref "RL83") (pin "4") (pintype "passive"))
    )
    (net (code "197") (name "unconnected-(RL83-Pad5)") (class "Default")
      (node (ref "RL83") (pin "5") (pintype "passive"))
    )
    (net (code "198") (name "unconnected-(RL83-Pad6)") (class "Default")
      (node (ref "RL83") (pin "6") (pintype "passive"))
    )
    (net (code "199") (name "unconnected-(RL84-Pad4)") (class "Default")
      (node (ref "RL84") (pin "4") (pintype "passive"))
    )
    (net (code "200") (name "unconnected-(RL84-Pad5)") (class "Default")
      (node (ref "RL84") (pin "5") (pintype "passive"))
    )
    (net (code "201") (name "unconnected-(RL84-Pad6)") (class "Default")
      (node (ref "RL84") (pin "6") (pintype "passive"))
    )
    (net (code "202") (name "unconnected-(RL85-Pad4)") (class "Default")
      (node (ref "RL85") (pin "4") (pintype "passive"))
    )
    (net (code "203") (name "unconnected-(RL85-Pad5)") (class "Default")
      (node (ref "RL85") (pin "5") (pintype "passive"))
    )
    (net (code "204") (name "unconnected-(RL85-Pad6)") (class "Default")
      (node (ref "RL85") (pin "6") (pintype "passive"))
    )
    (net (code "205") (name "unconnected-(RL86-Pad4)") (class "Default")
      (node (ref "RL86") (pin "4") (pintype "passive"))
    )
    (net (code "206") (name "unconnected-(RL86-Pad5)") (class "Default")
      (node (ref "RL86") (pin "5") (pintype "passive"))
    )
    (net (code "207") (name "unconnected-(RL86-Pad6)") (class "Default")
      (node (ref "RL86") (pin "6") (pintype "passive"))
    )
    (net (code "208") (name "unconnected-(RL87-Pad4)") (class "Default")
      (node (ref "RL87") (pin "4") (pintype "passive"))
    )
    (net (code "209") (name "unconnected-(RL87-Pad5)") (class "Default")
      (node (ref "RL87") (pin "5") (pintype "passive"))
    )
    (net (code "210") (name "unconnected-(RL87-Pad6)") (class "Default")
      (node (ref "RL87") (pin "6") (pintype "passive"))
    )
    (net (code "211") (name "unconnected-(RL88-Pad4)") (class "Default")
      (node (ref "RL88") (pin "4") (pintype "passive"))
    )
    (net (code "212") (name "unconnected-(RL88-Pad5)") (class "Default")
      (node (ref "RL88") (pin "5") (pintype "passive"))
    )
    (net (code "213") (name "unconnected-(RL88-Pad6)") (class "Default")
      (node (ref "RL88") (pin "6") (pintype "passive"))
    )
    (net (code "214") (name "unconnected-(RL89-Pad4)") (class "Default")
      (node (ref "RL89") (pin "4") (pintype "passive"))
    )
    (net (code "215") (name "unconnected-(RL89-Pad5)") (class "Default")
      (node (ref "RL89") (pin "5") (pintype "passive"))
    )
    (net (code "216") (name "unconnected-(RL89-Pad6)") (class "Default")
      (node (ref "RL89") (pin "6") (pintype "passive"))
    )
    (net (code "217") (name "unconnected-(RL90-Pad4)") (class "Default")
      (node (ref "RL90") (pin "4") (pintype "passive"))
    )
    (net (code "218") (name "unconnected-(RL90-Pad5)") (class "Default")
      (node (ref "RL90") (pin "5") (pintype "passive"))
    )
    (net (code "219") (name "unconnected-(RL90-Pad6)") (class "Default")
      (node (ref "RL90") (pin "6") (pintype "passive"))
    )
    (net (code "220") (name "unconnected-(RL91-Pad4)") (class "Default")
      (node (ref "RL91") (pin "4") (pintype "passive"))
    )
    (net (code "221") (name "unconnected-(RL91-Pad5)") (class "Default")
      (node (ref "RL91") (pin "5") (pintype "passive"))
    )
    (net (code "222") (name "unconnected-(RL91-Pad6)") (class "Default")
      (node (ref "RL91") (pin "6") (pintype "passive"))
    )
    (net (code "223") (name "unconnected-(RL92-Pad4)") (class "Default")
      (node (ref "RL92") (pin "4") (pintype "passive"))
    )
    (net (code "224") (name "unconnected-(RL92-Pad5)") (class "Default")
      (node (ref "RL92") (pin "5") (pintype "passive"))
    )
    (net (code "225") (name "unconnected-(RL92-Pad6)") (class "Default")
      (node (ref "RL92") (pin "6") (pintype "passive"))
    )
    (net (code "226") (name "unconnected-(RL93-Pad4)") (class "Default")
      (node (ref "RL93") (pin "4") (pintype "passive"))
    )
    (net (code "227") (name "unconnected-(RL93-Pad5)") (class "Default")
      (node (ref "RL93") (pin "5") (pintype "passive"))
    )
    (net (code "228") (name "unconnected-(RL93-Pad6)") (class "Default")
      (node (ref "RL93") (pin "6") (pintype "passive"))
    )
    (net (code "229") (name "unconnected-(RL94-Pad4)") (class "Default")
      (node (ref "RL94") (pin "4") (pintype "passive"))
    )
    (net (code "230") (name "unconnected-(RL94-Pad5)") (class "Default")
      (node (ref "RL94") (pin "5") (pintype "passive"))
    )
    (net (code "231") (name "unconnected-(RL94-Pad6)") (class "Default")
      (node (ref "RL94") (pin "6") (pintype "passive"))
    )
    (net (code "232") (name "unconnected-(RL95-Pad4)") (class "Default")
      (node (ref "RL95") (pin "4") (pintype "passive"))
    )
    (net (code "233") (name "unconnected-(RL95-Pad5)") (class "Default")
      (node (ref "RL95") (pin "5") (pintype "passive"))
    )
    (net (code "234") (name "unconnected-(RL95-Pad6)") (class "Default")
      (node (ref "RL95") (pin "6") (pintype "passive"))
    )
    (net (code "235") (name "unconnected-(RL96-Pad4)") (class "Default")
      (node (ref "RL96") (pin "4") (pintype "passive"))
    )
    (net (code "236") (name "unconnected-(RL96-Pad5)") (class "Default")
      (node (ref "RL96") (pin "5") (pintype "passive"))
    )
    (net (code "237") (name "unconnected-(RL96-Pad6)") (class "Default")
      (node (ref "RL96") (pin "6") (pintype "passive"))
    )
    (net (code "238") (name "unconnected-(RL97-Pad4)") (class "Default")
      (node (ref "RL97") (pin "4") (pintype "passive"))
    )
    (net (code "239") (name "unconnected-(RL97-Pad5)") (class "Default")
      (node (ref "RL97") (pin "5") (pintype "passive"))
    )
    (net (code "240") (name "unconnected-(RL97-Pad6)") (class "Default")
      (node (ref "RL97") (pin "6") (pintype "passive"))
    )
    (net (code "241") (name "unconnected-(RL98-Pad4)") (class "Default")
      (node (ref "RL98") (pin "4") (pintype "passive"))
    )
    (net (code "242") (name "unconnected-(RL98-Pad5)") (class "Default")
      (node (ref "RL98") (pin "5") (pintype "passive"))
    )
    (net (code "243") (name "unconnected-(RL98-Pad6)") (class "Default")
      (node (ref "RL98") (pin "6") (pintype "passive"))
    )
    (net (code "244") (name "unconnected-(RL99-Pad4)") (class "Default")
      (node (ref "RL99") (pin "4") (pintype "passive"))
    )
    (net (code "245") (name "unconnected-(RL99-Pad5)") (class "Default")
      (node (ref "RL99") (pin "5") (pintype "passive"))
    )
    (net (code "246") (name "unconnected-(RL99-Pad6)") (class "Default")
      (node (ref "RL99") (pin "6") (pintype "passive"))
    )
    (net (code "247") (name "unconnected-(RL100-Pad4)") (class "Default")
      (node (ref "RL100") (pin "4") (pintype "passive"))
    )
    (net (code "248") (name "unconnected-(RL100-Pad5)") (class "Default")
      (node (ref "RL100") (pin "5") (pintype "passive"))
    )
    (net (code "249") (name "unconnected-(RL100-Pad6)") (class "Default")
      (node (ref "RL100") (pin "6") (pintype "passive"))
    )
    (net (code "250") (name "unconnected-(RL101-Pad4)") (class "Default")
      (node (ref "RL101") (pin "4") (pintype "passive"))
    )
    (net (code "251") (name "unconnected-(RL101-Pad5)") (class "Default")
      (node (ref "RL101") (pin "5") (pintype "passive"))
    )
    (net (code "252") (name "unconnected-(RL101-Pad6)") (class "Default")
      (node (ref "RL101") (pin "6") (pintype "passive"))
    )
    (net (code "253") (name "unconnected-(RL102-Pad4)") (class "Default")
      (node (ref "RL102") (pin "4") (pintype "passive"))
    )
    (net (code "254") (name "unconnected-(RL102-Pad5)") (class "Default")
      (node (ref "RL102") (pin "5") (pintype "passive"))
    )
    (net (code "255") (name "unconnected-(RL102-Pad6)") (class "Default")
      (node (ref "RL102") (pin "6") (pintype "passive"))
    )
    (net (code "256") (name "unconnected-(RL103-Pad4)") (class "Default")
      (node (ref "RL103") (pin "4") (pintype "passive"))
    )
    (net (code "257") (name "unconnected-(RL103-Pad5)") (class "Default")
      (node (ref "RL103") (pin "5") (pintype "passive"))
    )
    (net (code "258") (name "unconnected-(RL103-Pad6)") (class "Default")
      (node (ref "RL103") (pin "6") (pintype "passive"))
    )
    (net (code "259") (name "unconnected-(RL104-Pad4)") (class "Default")
      (node (ref "RL104") (pin "4") (pintype "passive"))
    )
    (net (code "260") (name "unconnected-(RL104-Pad5)") (class "Default")
      (node (ref "RL104") (pin "5") (pintype "passive"))
    )
    (net (code "261") (name "unconnected-(RL104-Pad6)") (class "Default")
      (node (ref "RL104") (pin "6") (pintype "passive"))
    )
    (net (code "262") (name "unconnected-(RL105-Pad4)") (class "Default")
      (node (ref "RL105") (pin "4") (pintype "passive"))
    )
    (net (code "263") (name "unconnected-(RL105-Pad5)") (class "Default")
      (node (ref "RL105") (pin "5") (pintype "passive"))
    )
    (net (code "264") (name "unconnected-(RL105-Pad6)") (class "Default")
      (node (ref "RL105") (pin "6") (pintype "passive"))
    )
    (net (code "265") (name "unconnected-(RL106-Pad4)") (class "Default")
      (node (ref "RL106") (pin "4") (pintype "passive"))
    )
    (net (code "266") (name "unconnected-(RL106-Pad5)") (class "Default")
      (node (ref "RL106") (pin "5") (pintype "passive"))
    )
    (net (code "267") (name "unconnected-(RL106-Pad6)") (class "Default")
      (node (ref "RL106") (pin "6") (pintype "passive"))
    )
    (net (code "268") (name "unconnected-(RL107-Pad4)") (class "Default")
      (node (ref "RL107") (pin "4") (pintype "passive"))
    )
    (net (code "269") (name "unconnected-(RL107-Pad5)") (class "Default")
      (node (ref "RL107") (pin "5") (pintype "passive"))
    )
    (net (code "270") (name "unconnected-(RL107-Pad6)") (class "Default")
      (node (ref "RL107") (pin "6") (pintype "passive"))
    )
    (net (code "271") (name "unconnected-(RL108-Pad4)") (class "Default")
      (node (ref "RL108") (pin "4") (pintype "passive"))
    )
    (net (code "272") (name "unconnected-(RL108-Pad5)") (class "Default")
      (node (ref "RL108") (pin "5") (pintype "passive"))
    )
    (net (code "273") (name "unconnected-(RL108-Pad6)") (class "Default")
      (node (ref "RL108") (pin "6") (pintype "passive"))
    )
  )
)
